# half-pint-turbidimeter_led_wires.net
KiCad netlist of a schematic drawn in EAGLE
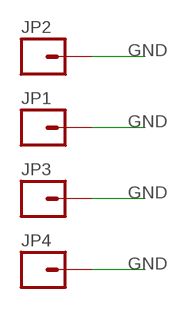
[diagram p0: schematic, sheet 1]

(export (version "E")
  (design (tool "Eeschema 10.0.6"))
  (components
    (comp (ref "JP1")
      (value "M01PTH")
      (footprint "eagle-import:1X01")
      (libsource (lib "eagle-import") (part "M01PTH"))
    )
    (comp (ref "JP2")
      (value "M01PTH")
      (footprint "eagle-import:1X01")
      (libsource (lib "eagle-import") (part "M01PTH"))
    )
    (comp (ref "JP3")
      (value "M01PTH")
      (footprint "eagle-import:1X01")
      (libsource (lib "eagle-import") (part "M01PTH"))
    )
    (comp (ref "JP4")
      (value "M01PTH")
      (footprint "eagle-import:1X01")
      (libsource (lib "eagle-import") (part "M01PTH"))
    )
  )
  (nets
    (net (code "1") (name "/GND") (class "Default")
      (node (ref "JP1") (pin "1") (pinfunction "1_1") (pintype "passive"))
      (node (ref "JP2") (pin "1") (pinfunction "1_1") (pintype "passive"))
      (node (ref "JP3") (pin "1") (pinfunction "1_1") (pintype "passive"))
      (node (ref "JP4") (pin "1") (pinfunction "1_1") (pintype "passive"))
    )
  )
)
